# Stepper-Controller.net
KiCad netlist of a schematic drawn in EAGLE
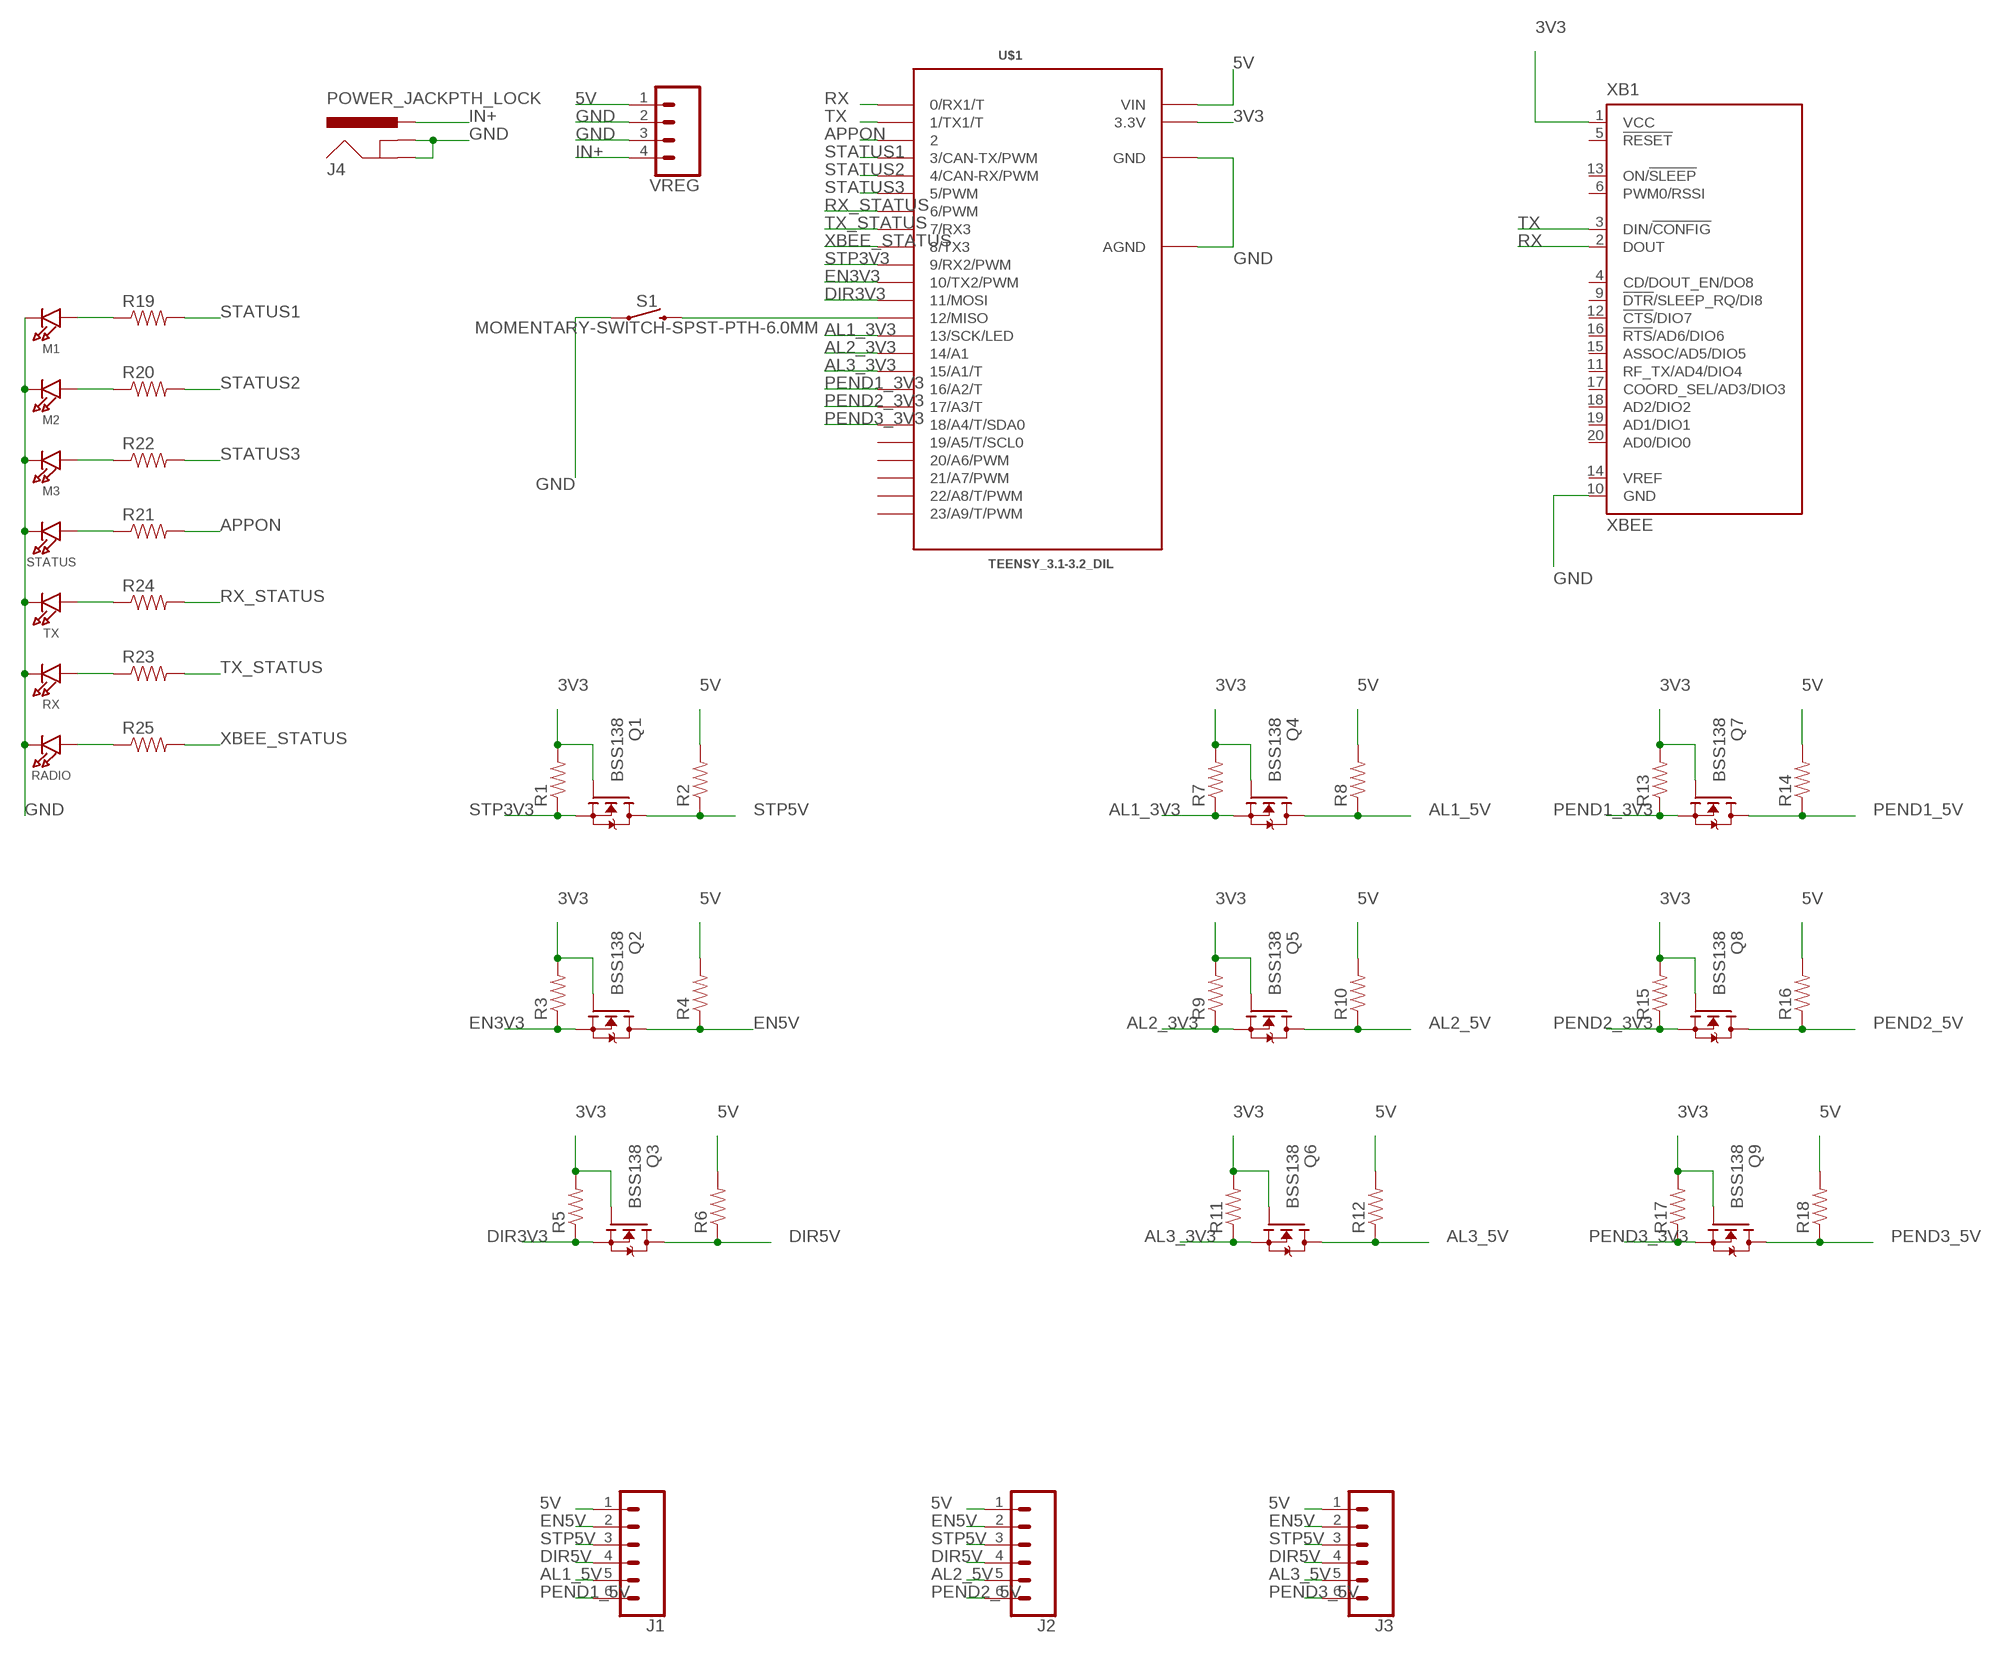
[diagram p0: schematic, sheet 1]

(export (version "E")
  (design (tool "Eeschema 10.0.6"))
  (components
    (comp (ref "J1")
      (value "CONN_06NO_SILK_FEMALE_PTH")
      (footprint "eagle-import:1X06_NO_SILK")
      (libsource (lib "eagle-import") (part "CONN_06NO_SILK_FEMALE_PTH"))
    )
    (comp (ref "J2")
      (value "CONN_06NO_SILK_FEMALE_PTH")
      (footprint "eagle-import:1X06_NO_SILK")
      (libsource (lib "eagle-import") (part "CONN_06NO_SILK_FEMALE_PTH"))
    )
    (comp (ref "J3")
      (value "CONN_06NO_SILK_FEMALE_PTH")
      (footprint "eagle-import:1X06_NO_SILK")
      (libsource (lib "eagle-import") (part "CONN_06NO_SILK_FEMALE_PTH"))
    )
    (comp (ref "J4")
      (value "POWER_JACKPTH_LOCK")
      (footprint "eagle-import:POWER_JACK_PTH_LOCK")
      (libsource (lib "eagle-import") (part "POWER_JACKPTH_LOCK"))
    )
    (comp (ref "M1")
      (value "MICROBUILDER_LED0603")
      (footprint "eagle-import:MICROBUILDER_CHIPLED_0603")
      (libsource (lib "eagle-import") (part "MICROBUILDER_LED0603"))
    )
    (comp (ref "M2")
      (value "MICROBUILDER_LED0603")
      (footprint "eagle-import:MICROBUILDER_CHIPLED_0603")
      (libsource (lib "eagle-import") (part "MICROBUILDER_LED0603"))
    )
    (comp (ref "M3")
      (value "MICROBUILDER_LED0603")
      (footprint "eagle-import:MICROBUILDER_CHIPLED_0603")
      (libsource (lib "eagle-import") (part "MICROBUILDER_LED0603"))
    )
    (comp (ref "Q1")
      (value "BSS138")
      (footprint "eagle-import:SOT23")
      (fields (field (name "MF") "Fairchild"))
      (libsource (lib "eagle-import") (part "BSS138"))
    )
    (comp (ref "Q2")
      (value "BSS138")
      (footprint "eagle-import:SOT23")
      (fields (field (name "MF") "Fairchild"))
      (libsource (lib "eagle-import") (part "BSS138"))
    )
    (comp (ref "Q3")
      (value "BSS138")
      (footprint "eagle-import:SOT23")
      (fields (field (name "MF") "Fairchild"))
      (libsource (lib "eagle-import") (part "BSS138"))
    )
    (comp (ref "Q4")
      (value "BSS138")
      (footprint "eagle-import:SOT23")
      (fields (field (name "MF") "Fairchild"))
      (libsource (lib "eagle-import") (part "BSS138"))
    )
    (comp (ref "Q5")
      (value "BSS138")
      (footprint "eagle-import:SOT23")
      (fields (field (name "MF") "Fairchild"))
      (libsource (lib "eagle-import") (part "BSS138"))
    )
    (comp (ref "Q6")
      (value "BSS138")
      (footprint "eagle-import:SOT23")
      (fields (field (name "MF") "Fairchild"))
      (libsource (lib "eagle-import") (part "BSS138"))
    )
    (comp (ref "Q7")
      (value "BSS138")
      (footprint "eagle-import:SOT23")
      (fields (field (name "MF") "Fairchild"))
      (libsource (lib "eagle-import") (part "BSS138"))
    )
    (comp (ref "Q8")
      (value "BSS138")
      (footprint "eagle-import:SOT23")
      (fields (field (name "MF") "Fairchild"))
      (libsource (lib "eagle-import") (part "BSS138"))
    )
    (comp (ref "Q9")
      (value "BSS138")
      (footprint "eagle-import:SOT23")
      (fields (field (name "MF") "Fairchild"))
      (libsource (lib "eagle-import") (part "BSS138"))
    )
    (comp (ref "R1")
      (value "CONTROLBOARD_V1.0_SPARKFUN_RESISTOR0603-RES")
      (footprint "eagle-import:CONTROLBOARD_V1.0_SPARKFUN_0603-RES")
      (libsource (lib "eagle-import") (part "CONTROLBOARD_V1.0_SPARKFUN_RESISTOR0603-RES"))
    )
    (comp (ref "R2")
      (value "CONTROLBOARD_V1.0_SPARKFUN_RESISTOR0603-RES")
      (footprint "eagle-import:CONTROLBOARD_V1.0_SPARKFUN_0603-RES")
      (libsource (lib "eagle-import") (part "CONTROLBOARD_V1.0_SPARKFUN_RESISTOR0603-RES"))
    )
    (comp (ref "R3")
      (value "CONTROLBOARD_V1.0_SPARKFUN_RESISTOR0603-RES")
      (footprint "eagle-import:CONTROLBOARD_V1.0_SPARKFUN_0603-RES")
      (libsource (lib "eagle-import") (part "CONTROLBOARD_V1.0_SPARKFUN_RESISTOR0603-RES"))
    )
    (comp (ref "R4")
      (value "CONTROLBOARD_V1.0_SPARKFUN_RESISTOR0603-RES")
      (footprint "eagle-import:CONTROLBOARD_V1.0_SPARKFUN_0603-RES")
      (libsource (lib "eagle-import") (part "CONTROLBOARD_V1.0_SPARKFUN_RESISTOR0603-RES"))
    )
    (comp (ref "R5")
      (value "CONTROLBOARD_V1.0_SPARKFUN_RESISTOR0603-RES")
      (footprint "eagle-import:CONTROLBOARD_V1.0_SPARKFUN_0603-RES")
      (libsource (lib "eagle-import") (part "CONTROLBOARD_V1.0_SPARKFUN_RESISTOR0603-RES"))
    )
    (comp (ref "R6")
      (value "CONTROLBOARD_V1.0_SPARKFUN_RESISTOR0603-RES")
      (footprint "eagle-import:CONTROLBOARD_V1.0_SPARKFUN_0603-RES")
      (libsource (lib "eagle-import") (part "CONTROLBOARD_V1.0_SPARKFUN_RESISTOR0603-RES"))
    )
    (comp (ref "R7")
      (value "CONTROLBOARD_V1.0_SPARKFUN_RESISTOR0603-RES")
      (footprint "eagle-import:CONTROLBOARD_V1.0_SPARKFUN_0603-RES")
      (libsource (lib "eagle-import") (part "CONTROLBOARD_V1.0_SPARKFUN_RESISTOR0603-RES"))
    )
    (comp (ref "R8")
      (value "CONTROLBOARD_V1.0_SPARKFUN_RESISTOR0603-RES")
      (footprint "eagle-import:CONTROLBOARD_V1.0_SPARKFUN_0603-RES")
      (libsource (lib "eagle-import") (part "CONTROLBOARD_V1.0_SPARKFUN_RESISTOR0603-RES"))
    )
    (comp (ref "R9")
      (value "CONTROLBOARD_V1.0_SPARKFUN_RESISTOR0603-RES")
      (footprint "eagle-import:CONTROLBOARD_V1.0_SPARKFUN_0603-RES")
      (libsource (lib "eagle-import") (part "CONTROLBOARD_V1.0_SPARKFUN_RESISTOR0603-RES"))
    )
    (comp (ref "R10")
      (value "CONTROLBOARD_V1.0_SPARKFUN_RESISTOR0603-RES")
      (footprint "eagle-import:CONTROLBOARD_V1.0_SPARKFUN_0603-RES")
      (libsource (lib "eagle-import") (part "CONTROLBOARD_V1.0_SPARKFUN_RESISTOR0603-RES"))
    )
    (comp (ref "R11")
      (value "CONTROLBOARD_V1.0_SPARKFUN_RESISTOR0603-RES")
      (footprint "eagle-import:CONTROLBOARD_V1.0_SPARKFUN_0603-RES")
      (libsource (lib "eagle-import") (part "CONTROLBOARD_V1.0_SPARKFUN_RESISTOR0603-RES"))
    )
    (comp (ref "R12")
      (value "CONTROLBOARD_V1.0_SPARKFUN_RESISTOR0603-RES")
      (footprint "eagle-import:CONTROLBOARD_V1.0_SPARKFUN_0603-RES")
      (libsource (lib "eagle-import") (part "CONTROLBOARD_V1.0_SPARKFUN_RESISTOR0603-RES"))
    )
    (comp (ref "R13")
      (value "CONTROLBOARD_V1.0_SPARKFUN_RESISTOR0603-RES")
      (footprint "eagle-import:CONTROLBOARD_V1.0_SPARKFUN_0603-RES")
      (libsource (lib "eagle-import") (part "CONTROLBOARD_V1.0_SPARKFUN_RESISTOR0603-RES"))
    )
    (comp (ref "R14")
      (value "CONTROLBOARD_V1.0_SPARKFUN_RESISTOR0603-RES")
      (footprint "eagle-import:CONTROLBOARD_V1.0_SPARKFUN_0603-RES")
      (libsource (lib "eagle-import") (part "CONTROLBOARD_V1.0_SPARKFUN_RESISTOR0603-RES"))
    )
    (comp (ref "R15")
      (value "CONTROLBOARD_V1.0_SPARKFUN_RESISTOR0603-RES")
      (footprint "eagle-import:CONTROLBOARD_V1.0_SPARKFUN_0603-RES")
      (libsource (lib "eagle-import") (part "CONTROLBOARD_V1.0_SPARKFUN_RESISTOR0603-RES"))
    )
    (comp (ref "R16")
      (value "CONTROLBOARD_V1.0_SPARKFUN_RESISTOR0603-RES")
      (footprint "eagle-import:CONTROLBOARD_V1.0_SPARKFUN_0603-RES")
      (libsource (lib "eagle-import") (part "CONTROLBOARD_V1.0_SPARKFUN_RESISTOR0603-RES"))
    )
    (comp (ref "R17")
      (value "CONTROLBOARD_V1.0_SPARKFUN_RESISTOR0603-RES")
      (footprint "eagle-import:CONTROLBOARD_V1.0_SPARKFUN_0603-RES")
      (libsource (lib "eagle-import") (part "CONTROLBOARD_V1.0_SPARKFUN_RESISTOR0603-RES"))
    )
    (comp (ref "R18")
      (value "CONTROLBOARD_V1.0_SPARKFUN_RESISTOR0603-RES")
      (footprint "eagle-import:CONTROLBOARD_V1.0_SPARKFUN_0603-RES")
      (libsource (lib "eagle-import") (part "CONTROLBOARD_V1.0_SPARKFUN_RESISTOR0603-RES"))
    )
    (comp (ref "R19")
      (value "CONTROLBOARD_V1.0_SPARKFUN_RESISTOR0603-RES")
      (footprint "eagle-import:CONTROLBOARD_V1.0_SPARKFUN_0603-RES")
      (libsource (lib "eagle-import") (part "CONTROLBOARD_V1.0_SPARKFUN_RESISTOR0603-RES"))
    )
    (comp (ref "R20")
      (value "CONTROLBOARD_V1.0_SPARKFUN_RESISTOR0603-RES")
      (footprint "eagle-import:CONTROLBOARD_V1.0_SPARKFUN_0603-RES")
      (libsource (lib "eagle-import") (part "CONTROLBOARD_V1.0_SPARKFUN_RESISTOR0603-RES"))
    )
    (comp (ref "R21")
      (value "CONTROLBOARD_V1.0_SPARKFUN_RESISTOR0603-RES")
      (footprint "eagle-import:CONTROLBOARD_V1.0_SPARKFUN_0603-RES")
      (libsource (lib "eagle-import") (part "CONTROLBOARD_V1.0_SPARKFUN_RESISTOR0603-RES"))
    )
    (comp (ref "R22")
      (value "CONTROLBOARD_V1.0_SPARKFUN_RESISTOR0603-RES")
      (footprint "eagle-import:CONTROLBOARD_V1.0_SPARKFUN_0603-RES")
      (libsource (lib "eagle-import") (part "CONTROLBOARD_V1.0_SPARKFUN_RESISTOR0603-RES"))
    )
    (comp (ref "R23")
      (value "CONTROLBOARD_V1.0_SPARKFUN_RESISTOR0603-RES")
      (footprint "eagle-import:CONTROLBOARD_V1.0_SPARKFUN_0603-RES")
      (libsource (lib "eagle-import") (part "CONTROLBOARD_V1.0_SPARKFUN_RESISTOR0603-RES"))
    )
    (comp (ref "R24")
      (value "CONTROLBOARD_V1.0_SPARKFUN_RESISTOR0603-RES")
      (footprint "eagle-import:CONTROLBOARD_V1.0_SPARKFUN_0603-RES")
      (libsource (lib "eagle-import") (part "CONTROLBOARD_V1.0_SPARKFUN_RESISTOR0603-RES"))
    )
    (comp (ref "R25")
      (value "CONTROLBOARD_V1.0_SPARKFUN_RESISTOR0603-RES")
      (footprint "eagle-import:CONTROLBOARD_V1.0_SPARKFUN_0603-RES")
      (libsource (lib "eagle-import") (part "CONTROLBOARD_V1.0_SPARKFUN_RESISTOR0603-RES"))
    )
    (comp (ref "RADIO")
      (value "MICROBUILDER_LED0603")
      (footprint "eagle-import:MICROBUILDER_CHIPLED_0603")
      (libsource (lib "eagle-import") (part "MICROBUILDER_LED0603"))
    )
    (comp (ref "RX")
      (value "MICROBUILDER_LED0603")
      (footprint "eagle-import:MICROBUILDER_CHIPLED_0603")
      (libsource (lib "eagle-import") (part "MICROBUILDER_LED0603"))
    )
    (comp (ref "S1")
      (value "MOMENTARY-SWITCH-SPST-PTH-6.0MM")
      (footprint "eagle-import:TACTILE_SWITCH_PTH_6.0MM")
      (libsource (lib "eagle-import") (part "MOMENTARY-SWITCH-SPST-PTH-6.0MM"))
    )
    (comp (ref "STATUS")
      (value "MICROBUILDER_LED0603")
      (footprint "eagle-import:MICROBUILDER_CHIPLED_0603")
      (libsource (lib "eagle-import") (part "MICROBUILDER_LED0603"))
    )
    (comp (ref "TX")
      (value "MICROBUILDER_LED0603")
      (footprint "eagle-import:MICROBUILDER_CHIPLED_0603")
      (libsource (lib "eagle-import") (part "MICROBUILDER_LED0603"))
    )
    (comp (ref "U$1")
      (value "TEENSY_3.1-3.2_DIL")
      (footprint "eagle-import:TEENSY_3.0-3.2&LC_DIL")
      (libsource (lib "eagle-import") (part "TEENSY_3.1-3.2_DIL"))
    )
    (comp (ref "VREG")
      (value "CONN_04LONGPADS")
      (footprint "eagle-import:1X04_LONGPADS")
      (libsource (lib "eagle-import") (part "CONN_04LONGPADS"))
    )
    (comp (ref "XB1")
      (value "XBEE")
      (footprint "eagle-import:XBEE")
      (fields (field (name "MPN") "XBP24-Z7UIT-004"))
      (libsource (lib "eagle-import") (part "XBEE"))
    )
  )
  (nets
    (net (code "1") (name "/3V3") (class "Default")
      (node (ref "Q1") (pin "1") (pinfunction "G_1") (pintype "passive"))
      (node (ref "Q2") (pin "1") (pinfunction "G_1") (pintype "passive"))
      (node (ref "Q3") (pin "1") (pinfunction "G_1") (pintype "passive"))
      (node (ref "Q4") (pin "1") (pinfunction "G_1") (pintype "passive"))
      (node (ref "Q5") (pin "1") (pinfunction "G_1") (pintype "passive"))
      (node (ref "Q6") (pin "1") (pinfunction "G_1") (pintype "passive"))
      (node (ref "Q7") (pin "1") (pinfunction "G_1") (pintype "passive"))
      (node (ref "Q8") (pin "1") (pinfunction "G_1") (pintype "passive"))
      (node (ref "Q9") (pin "1") (pinfunction "G_1") (pintype "passive"))
      (node (ref "R1") (pin "2") (pinfunction "2_2") (pintype "passive"))
      (node (ref "R11") (pin "2") (pinfunction "2_2") (pintype "passive"))
      (node (ref "R13") (pin "2") (pinfunction "2_2") (pintype "passive"))
      (node (ref "R15") (pin "2") (pinfunction "2_2") (pintype "passive"))
      (node (ref "R17") (pin "2") (pinfunction "2_2") (pintype "passive"))
      (node (ref "R3") (pin "2") (pinfunction "2_2") (pintype "passive"))
      (node (ref "R5") (pin "2") (pinfunction "2_2") (pintype "passive"))
      (node (ref "R7") (pin "2") (pinfunction "2_2") (pintype "passive"))
      (node (ref "R9") (pin "2") (pinfunction "2_2") (pintype "passive"))
      (node (ref "U$1") (pin "3.3V") (pinfunction "3.3V_3.3V") (pintype "power_in"))
      (node (ref "XB1") (pin "1") (pinfunction "VCC_1") (pintype "power_in"))
    )
    (net (code "2") (name "/5V") (class "Default")
      (node (ref "J1") (pin "1") (pinfunction "1_1") (pintype "passive"))
      (node (ref "J2") (pin "1") (pinfunction "1_1") (pintype "passive"))
      (node (ref "J3") (pin "1") (pinfunction "1_1") (pintype "passive"))
      (node (ref "R10") (pin "2") (pinfunction "2_2") (pintype "passive"))
      (node (ref "R12") (pin "2") (pinfunction "2_2") (pintype "passive"))
      (node (ref "R14") (pin "2") (pinfunction "2_2") (pintype "passive"))
      (node (ref "R16") (pin "2") (pinfunction "2_2") (pintype "passive"))
      (node (ref "R18") (pin "2") (pinfunction "2_2") (pintype "passive"))
      (node (ref "R2") (pin "2") (pinfunction "2_2") (pintype "passive"))
      (node (ref "R4") (pin "2") (pinfunction "2_2") (pintype "passive"))
      (node (ref "R6") (pin "2") (pinfunction "2_2") (pintype "passive"))
      (node (ref "R8") (pin "2") (pinfunction "2_2") (pintype "passive"))
      (node (ref "U$1") (pin "VIN") (pinfunction "VIN_VIN") (pintype "power_in"))
      (node (ref "VREG") (pin "1") (pinfunction "1_1") (pintype "passive"))
    )
    (net (code "3") (name "/AL1_3V3") (class "Default")
      (node (ref "Q4") (pin "2") (pinfunction "S_2") (pintype "passive"))
      (node (ref "R7") (pin "1") (pinfunction "1_1") (pintype "passive"))
      (node (ref "U$1") (pin "13") (pinfunction "13/SCK/LED_13") (pintype "bidirectional"))
    )
    (net (code "4") (name "/AL1_5V") (class "Default")
      (node (ref "J1") (pin "5") (pinfunction "5_5") (pintype "passive"))
      (node (ref "Q4") (pin "3") (pinfunction "D_3") (pintype "passive"))
      (node (ref "R8") (pin "1") (pinfunction "1_1") (pintype "passive"))
    )
    (net (code "5") (name "/AL2_3V3") (class "Default")
      (node (ref "Q5") (pin "2") (pinfunction "S_2") (pintype "passive"))
      (node (ref "R9") (pin "1") (pinfunction "1_1") (pintype "passive"))
      (node (ref "U$1") (pin "14/A0") (pinfunction "14/A1_14/A0") (pintype "bidirectional"))
    )
    (net (code "6") (name "/AL2_5V") (class "Default")
      (node (ref "J2") (pin "5") (pinfunction "5_5") (pintype "passive"))
      (node (ref "Q5") (pin "3") (pinfunction "D_3") (pintype "passive"))
      (node (ref "R10") (pin "1") (pinfunction "1_1") (pintype "passive"))
    )
    (net (code "7") (name "/AL3_3V3") (class "Default")
      (node (ref "Q6") (pin "2") (pinfunction "S_2") (pintype "passive"))
      (node (ref "R11") (pin "1") (pinfunction "1_1") (pintype "passive"))
      (node (ref "U$1") (pin "15/A1") (pinfunction "15/A1/T_15/A1") (pintype "bidirectional"))
    )
    (net (code "8") (name "/AL3_5V") (class "Default")
      (node (ref "J3") (pin "5") (pinfunction "5_5") (pintype "passive"))
      (node (ref "Q6") (pin "3") (pinfunction "D_3") (pintype "passive"))
      (node (ref "R12") (pin "1") (pinfunction "1_1") (pintype "passive"))
    )
    (net (code "9") (name "/APPON") (class "Default")
      (node (ref "R21") (pin "2") (pinfunction "2_2") (pintype "passive"))
      (node (ref "U$1") (pin "2") (pinfunction "2_2") (pintype "bidirectional"))
    )
    (net (code "10") (name "/DIR3V3") (class "Default")
      (node (ref "Q3") (pin "2") (pinfunction "S_2") (pintype "passive"))
      (node (ref "R5") (pin "1") (pinfunction "1_1") (pintype "passive"))
      (node (ref "U$1") (pin "11") (pinfunction "11/MOSI_11") (pintype "bidirectional"))
    )
    (net (code "11") (name "/DIR5V") (class "Default")
      (node (ref "J1") (pin "4") (pinfunction "4_4") (pintype "passive"))
      (node (ref "J2") (pin "4") (pinfunction "4_4") (pintype "passive"))
      (node (ref "J3") (pin "4") (pinfunction "4_4") (pintype "passive"))
      (node (ref "Q3") (pin "3") (pinfunction "D_3") (pintype "passive"))
      (node (ref "R6") (pin "1") (pinfunction "1_1") (pintype "passive"))
    )
    (net (code "12") (name "/EN3V3") (class "Default")
      (node (ref "Q2") (pin "2") (pinfunction "S_2") (pintype "passive"))
      (node (ref "R3") (pin "1") (pinfunction "1_1") (pintype "passive"))
      (node (ref "U$1") (pin "10") (pinfunction "10/TX2/PWM_10") (pintype "bidirectional"))
    )
    (net (code "13") (name "/EN5V") (class "Default")
      (node (ref "J1") (pin "2") (pinfunction "2_2") (pintype "passive"))
      (node (ref "J2") (pin "2") (pinfunction "2_2") (pintype "passive"))
      (node (ref "J3") (pin "2") (pinfunction "2_2") (pintype "passive"))
      (node (ref "Q2") (pin "3") (pinfunction "D_3") (pintype "passive"))
      (node (ref "R4") (pin "1") (pinfunction "1_1") (pintype "passive"))
    )
    (net (code "14") (name "/GND") (class "Default")
      (node (ref "J4") (pin "GND") (pinfunction "GND_GND") (pintype "bidirectional"))
      (node (ref "J4") (pin "GNDBREAK") (pinfunction "GNDBREAK_GNDBREAK") (pintype "bidirectional"))
      (node (ref "M1") (pin "C") (pinfunction "C_C") (pintype "passive"))
      (node (ref "M2") (pin "C") (pinfunction "C_C") (pintype "passive"))
      (node (ref "M3") (pin "C") (pinfunction "C_C") (pintype "passive"))
      (node (ref "RADIO") (pin "C") (pinfunction "C_C") (pintype "passive"))
      (node (ref "RX") (pin "C") (pinfunction "C_C") (pintype "passive"))
      (node (ref "S1") (pin "1") (pinfunction "1_1") (pintype "passive"))
      (node (ref "STATUS") (pin "C") (pinfunction "C_C") (pintype "passive"))
      (node (ref "TX") (pin "C") (pinfunction "C_C") (pintype "passive"))
      (node (ref "U$1") (pin "AGND") (pinfunction "AGND_AGND") (pintype "power_in"))
      (node (ref "U$1") (pin "GND") (pinfunction "GND_GND") (pintype "power_in"))
      (node (ref "VREG") (pin "2") (pinfunction "2_2") (pintype "passive"))
      (node (ref "VREG") (pin "3") (pinfunction "3_3") (pintype "passive"))
      (node (ref "XB1") (pin "10") (pinfunction "GND_10") (pintype "power_in"))
    )
    (net (code "15") (name "/IN+") (class "Default")
      (node (ref "J4") (pin "PWR") (pinfunction "PWR_PWR") (pintype "bidirectional"))
      (node (ref "VREG") (pin "4") (pinfunction "4_4") (pintype "passive"))
    )
    (net (code "16") (name "/PEND1_3V3") (class "Default")
      (node (ref "Q7") (pin "2") (pinfunction "S_2") (pintype "passive"))
      (node (ref "R13") (pin "1") (pinfunction "1_1") (pintype "passive"))
      (node (ref "U$1") (pin "16/A2") (pinfunction "16/A2/T_16/A2") (pintype "bidirectional"))
    )
    (net (code "17") (name "/PEND1_5V") (class "Default")
      (node (ref "J1") (pin "6") (pinfunction "6_6") (pintype "passive"))
      (node (ref "Q7") (pin "3") (pinfunction "D_3") (pintype "passive"))
      (node (ref "R14") (pin "1") (pinfunction "1_1") (pintype "passive"))
    )
    (net (code "18") (name "/PEND2_3V3") (class "Default")
      (node (ref "Q8") (pin "2") (pinfunction "S_2") (pintype "passive"))
      (node (ref "R15") (pin "1") (pinfunction "1_1") (pintype "passive"))
      (node (ref "U$1") (pin "17/A3") (pinfunction "17/A3/T_17/A3") (pintype "bidirectional"))
    )
    (net (code "19") (name "/PEND2_5V") (class "Default")
      (node (ref "J2") (pin "6") (pinfunction "6_6") (pintype "passive"))
      (node (ref "Q8") (pin "3") (pinfunction "D_3") (pintype "passive"))
      (node (ref "R16") (pin "1") (pinfunction "1_1") (pintype "passive"))
    )
    (net (code "20") (name "/PEND3_3V3") (class "Default")
      (node (ref "Q9") (pin "2") (pinfunction "S_2") (pintype "passive"))
      (node (ref "R17") (pin "1") (pinfunction "1_1") (pintype "passive"))
      (node (ref "U$1") (pin "18/A4") (pinfunction "18/A4/T/SDA0_18/A4") (pintype "bidirectional"))
    )
    (net (code "21") (name "/PEND3_5V") (class "Default")
      (node (ref "J3") (pin "6") (pinfunction "6_6") (pintype "passive"))
      (node (ref "Q9") (pin "3") (pinfunction "D_3") (pintype "passive"))
      (node (ref "R18") (pin "1") (pinfunction "1_1") (pintype "passive"))
    )
    (net (code "22") (name "/RX") (class "Default")
      (node (ref "U$1") (pin "0") (pinfunction "0/RX1/T_0") (pintype "bidirectional"))
      (node (ref "XB1") (pin "2") (pinfunction "DOUT_2") (pintype "output"))
    )
    (net (code "23") (name "/RX_STATUS") (class "Default")
      (node (ref "R24") (pin "2") (pinfunction "2_2") (pintype "passive"))
      (node (ref "U$1") (pin "6") (pinfunction "6/PWM_6") (pintype "bidirectional"))
    )
    (net (code "24") (name "/STATUS1") (class "Default")
      (node (ref "R19") (pin "2") (pinfunction "2_2") (pintype "passive"))
      (node (ref "U$1") (pin "3") (pinfunction "3/CAN-TX/PWM_3") (pintype "bidirectional"))
    )
    (net (code "25") (name "/STATUS2") (class "Default")
      (node (ref "R20") (pin "2") (pinfunction "2_2") (pintype "passive"))
      (node (ref "U$1") (pin "4") (pinfunction "4/CAN-RX/PWM_4") (pintype "bidirectional"))
    )
    (net (code "26") (name "/STATUS3") (class "Default")
      (node (ref "R22") (pin "2") (pinfunction "2_2") (pintype "passive"))
      (node (ref "U$1") (pin "5") (pinfunction "5/PWM_5") (pintype "bidirectional"))
    )
    (net (code "27") (name "/STP3V3") (class "Default")
      (node (ref "Q1") (pin "2") (pinfunction "S_2") (pintype "passive"))
      (node (ref "R1") (pin "1") (pinfunction "1_1") (pintype "passive"))
      (node (ref "U$1") (pin "9") (pinfunction "9/RX2/PWM_9") (pintype "bidirectional"))
    )
    (net (code "28") (name "/STP5V") (class "Default")
      (node (ref "J1") (pin "3") (pinfunction "3_3") (pintype "passive"))
      (node (ref "J2") (pin "3") (pinfunction "3_3") (pintype "passive"))
      (node (ref "J3") (pin "3") (pinfunction "3_3") (pintype "passive"))
      (node (ref "Q1") (pin "3") (pinfunction "D_3") (pintype "passive"))
      (node (ref "R2") (pin "1") (pinfunction "1_1") (pintype "passive"))
    )
    (net (code "29") (name "/TX") (class "Default")
      (node (ref "U$1") (pin "1") (pinfunction "1/TX1/T_1") (pintype "bidirectional"))
      (node (ref "XB1") (pin "3") (pinfunction "DIN/~{CONFIG}_3") (pintype "input"))
    )
    (net (code "30") (name "/TX_STATUS") (class "Default")
      (node (ref "R23") (pin "2") (pinfunction "2_2") (pintype "passive"))
      (node (ref "U$1") (pin "7") (pinfunction "7/RX3_7") (pintype "bidirectional"))
    )
    (net (code "31") (name "/XBEE_STATUS") (class "Default")
      (node (ref "R25") (pin "2") (pinfunction "2_2") (pintype "passive"))
      (node (ref "U$1") (pin "8") (pinfunction "8/TX3_8") (pintype "bidirectional"))
    )
    (net (code "32") (name "Net-(M1-PadA)") (class "Default")
      (node (ref "M1") (pin "A") (pinfunction "A_A") (pintype "passive"))
      (node (ref "R19") (pin "1") (pinfunction "1_1") (pintype "passive"))
    )
    (net (code "33") (name "Net-(M2-PadA)") (class "Default")
      (node (ref "M2") (pin "A") (pinfunction "A_A") (pintype "passive"))
      (node (ref "R20") (pin "1") (pinfunction "1_1") (pintype "passive"))
    )
    (net (code "34") (name "Net-(M3-PadA)") (class "Default")
      (node (ref "M3") (pin "A") (pinfunction "A_A") (pintype "passive"))
      (node (ref "R22") (pin "1") (pinfunction "1_1") (pintype "passive"))
    )
    (net (code "35") (name "Net-(R21-Pad1)") (class "Default")
      (node (ref "R21") (pin "1") (pinfunction "1_1") (pintype "passive"))
      (node (ref "STATUS") (pin "A") (pinfunction "A_A") (pintype "passive"))
    )
    (net (code "36") (name "Net-(R23-Pad1)") (class "Default")
      (node (ref "R23") (pin "1") (pinfunction "1_1") (pintype "passive"))
      (node (ref "RX") (pin "A") (pinfunction "A_A") (pintype "passive"))
    )
    (net (code "37") (name "Net-(R24-Pad1)") (class "Default")
      (node (ref "R24") (pin "1") (pinfunction "1_1") (pintype "passive"))
      (node (ref "TX") (pin "A") (pinfunction "A_A") (pintype "passive"))
    )
    (net (code "38") (name "Net-(R25-Pad1)") (class "Default")
      (node (ref "R25") (pin "1") (pinfunction "1_1") (pintype "passive"))
      (node (ref "RADIO") (pin "A") (pinfunction "A_A") (pintype "passive"))
    )
    (net (code "39") (name "Net-(S1-2)") (class "Default")
      (node (ref "S1") (pin "3") (pinfunction "2_3") (pintype "passive"))
      (node (ref "U$1") (pin "12") (pinfunction "12/MISO_12") (pintype "bidirectional"))
    )
    (net (code "40") (name "unconnected-(U$1-19{slash}A5{slash}T{slash}SCL0-Pad19{slash}A5)") (class "Default")
      (node (ref "U$1") (pin "19/A5") (pinfunction "19/A5/T/SCL0_19/A5") (pintype "bidirectional"))
    )
    (net (code "41") (name "unconnected-(U$1-20{slash}A6{slash}PWM-Pad20{slash}A6)") (class "Default")
      (node (ref "U$1") (pin "20/A6") (pinfunction "20/A6/PWM_20/A6") (pintype "bidirectional"))
    )
    (net (code "42") (name "unconnected-(U$1-21{slash}A7{slash}PWM-Pad21{slash}A7)") (class "Default")
      (node (ref "U$1") (pin "21/A7") (pinfunction "21/A7/PWM_21/A7") (pintype "bidirectional"))
    )
    (net (code "43") (name "unconnected-(U$1-22{slash}A8{slash}T{slash}PWM-Pad22{slash}A8)") (class "Default")
      (node (ref "U$1") (pin "22/A8") (pinfunction "22/A8/T/PWM_22/A8") (pintype "bidirectional"))
    )
    (net (code "44") (name "unconnected-(U$1-23{slash}A9{slash}T{slash}PWM-Pad23{slash}A9)") (class "Default")
      (node (ref "U$1") (pin "23/A9") (pinfunction "23/A9/T/PWM_23/A9") (pintype "bidirectional"))
    )
    (net (code "45") (name "unconnected-(XB1-AD0{slash}DIO0-Pad20)") (class "Default")
      (node (ref "XB1") (pin "20") (pinfunction "AD0/DIO0_20") (pintype "bidirectional"))
    )
    (net (code "46") (name "unconnected-(XB1-AD1{slash}DIO1-Pad19)") (class "Default")
      (node (ref "XB1") (pin "19") (pinfunction "AD1/DIO1_19") (pintype "bidirectional"))
    )
    (net (code "47") (name "unconnected-(XB1-AD2{slash}DIO2-Pad18)") (class "Default")
      (node (ref "XB1") (pin "18") (pinfunction "AD2/DIO2_18") (pintype "bidirectional"))
    )
    (net (code "48") (name "unconnected-(XB1-ASSOC{slash}AD5{slash}DIO5-Pad15)") (class "Default")
      (node (ref "XB1") (pin "15") (pinfunction "ASSOC/AD5/DIO5_15") (pintype "bidirectional"))
    )
    (net (code "49") (name "unconnected-(XB1-CD{slash}DOUT_EN{slash}DO8-Pad4)") (class "Default")
      (node (ref "XB1") (pin "4") (pinfunction "CD/DOUT_EN/DO8_4") (pintype "output"))
    )
    (net (code "50") (name "unconnected-(XB1-COORD_SEL{slash}AD3{slash}DIO3-Pad17)") (class "Default")
      (node (ref "XB1") (pin "17") (pinfunction "COORD_SEL/AD3/DIO3_17") (pintype "bidirectional"))
    )
    (net (code "51") (name "unconnected-(XB1-ON{slash}~{SLEEP}-Pad13)") (class "Default")
      (node (ref "XB1") (pin "13") (pinfunction "ON/~{SLEEP}_13") (pintype "output"))
    )
    (net (code "52") (name "unconnected-(XB1-PWM0{slash}RSSI-Pad6)") (class "Default")
      (node (ref "XB1") (pin "6") (pinfunction "PWM0/RSSI_6") (pintype "output"))
    )
    (net (code "53") (name "unconnected-(XB1-RF_TX{slash}AD4{slash}DIO4-Pad11)") (class "Default")
      (node (ref "XB1") (pin "11") (pinfunction "RF_TX/AD4/DIO4_11") (pintype "bidirectional"))
    )
    (net (code "54") (name "unconnected-(XB1-VREF-Pad14)") (class "Default")
      (node (ref "XB1") (pin "14") (pinfunction "VREF_14") (pintype "input"))
    )
    (net (code "55") (name "unconnected-(XB1-~{CTS}{slash}DIO7-Pad12)") (class "Default")
      (node (ref "XB1") (pin "12") (pinfunction "~{CTS}/DIO7_12") (pintype "bidirectional"))
    )
    (net (code "56") (name "unconnected-(XB1-~{DTR}{slash}SLEEP_RQ{slash}DI8-Pad9)") (class "Default")
      (node (ref "XB1") (pin "9") (pinfunction "~{DTR}/SLEEP_RQ/DI8_9") (pintype "bidirectional"))
    )
    (net (code "57") (name "unconnected-(XB1-~{RESET}-Pad5)") (class "Default")
      (node (ref "XB1") (pin "5") (pinfunction "~{RESET}_5") (pintype "input"))
    )
    (net (code "58") (name "unconnected-(XB1-~{RTS}{slash}AD6{slash}DIO6-Pad16)") (class "Default")
      (node (ref "XB1") (pin "16") (pinfunction "~{RTS}/AD6/DIO6_16") (pintype "bidirectional"))
    )
  )
)
